# Programming_Interface.net
KiCad netlist of a schematic drawn in Altium Designer
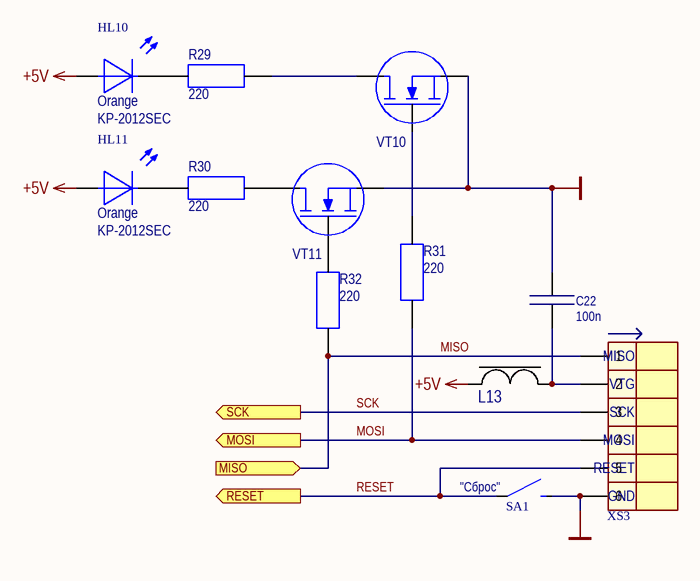
[diagram p0: Programming_Interface.SchDoc]

(export (version "E")
  (design (tool "Eeschema 10.0.6"))
  (components
    (comp (ref "C22")
      (value "100n")
      (footprint "SMDRC0805")
      (description "Generic capasitor non-polar")
      (fields (field (name "PARTNUMBER") "Capacitor 0805 100n"))
      (libsource (lib "library") (part "Capacitor"))
    )
    (comp (ref "HL10")
      (value "Orange")
      (footprint "Indicator:DIOMELF2012M")
      (description "Diod LED SMD Orange")
      (fields (field (name "MANUFACTURERPARTNUMBER") "KP-2012SEC"))
      (libsource (lib "Indicator") (part "LED1_O"))
    )
    (comp (ref "HL11")
      (value "Orange")
      (footprint "Indicator:DIOMELF2012M")
      (description "Diod LED SMD Orange")
      (fields (field (name "MANUFACTURERPARTNUMBER") "KP-2012SEC"))
      (libsource (lib "Indicator") (part "LED1_O"))
    )
    (comp (ref "L13")
      (value "MPZ1608S181A")
      (footprint "Inductor:INDC0603X03M")
      (description "Ferrite Bead")
      (libsource (lib "Inductor") (part "Ferrite Bead"))
    )
    (comp (ref "R29")
      (value "220")
      (footprint "SMDRC0805")
      (description "Generic resistor")
      (fields (field (name "PARTNUMBER") "Resistor 0805 220"))
      (libsource (lib "") (part "Resistor_1"))
    )
    (comp (ref "R30")
      (value "220")
      (footprint "SMDRC0805")
      (description "Generic resistor")
      (fields (field (name "PARTNUMBER") "Resistor 0805 220"))
      (libsource (lib "") (part "Resistor_1"))
    )
    (comp (ref "R31")
      (value "220")
      (footprint "SMDRC0805")
      (description "Generic resistor")
      (fields (field (name "PARTNUMBER") "Resistor 0805 220"))
      (libsource (lib "library") (part "Resistor"))
    )
    (comp (ref "R32")
      (value "220")
      (footprint "SMDRC0805")
      (description "Generic resistor")
      (fields (field (name "PARTNUMBER") "Resistor 0805 220"))
      (libsource (lib "library") (part "Resistor"))
    )
    (comp (ref "SA1")
      (value "DTSM20-4.3")
      (footprint "Switch:DTSM20")
      (description "Switch open")
      (fields (field (name "MANUFACTURER") "Diptronics"))
      (libsource (lib "Switch") (part "Switch1_DTSM20-4.3"))
    )
    (comp (ref "VT10")
      (value "2N7002")
      (footprint "Standard:SOT23 (TO-236AB)")
      (description "60V, 300mA N-channel Trench MOSFET")
      (libsource (lib "Transistor") (part "2N7002 n-MOSFET"))
    )
    (comp (ref "VT11")
      (value "2N7002")
      (footprint "Standard:SOT23 (TO-236AB)")
      (description "60V, 300mA N-channel Trench MOSFET")
      (libsource (lib "Transistor") (part "2N7002 n-MOSFET"))
    )
    (comp (ref "XS3")
      (value "IDC-06M")
      (footprint "Connector:IDC-06M")
      (description "SPI connector")
      (libsource (lib "Connector") (part "Con6_M IDC-06M_SPI"))
    )
  )
  (nets
    (net (code "1") (name "+5V") (class "Default")
      (node (ref "HL10") (pin "1") (pinfunction "1_1") (pintype "passive"))
      (node (ref "HL11") (pin "1") (pinfunction "1_1") (pintype "passive"))
      (node (ref "L13") (pin "1") (pinfunction "1_1") (pintype "passive"))
    )
    (net (code "2") (name "/MISO") (class "Default")
      (node (ref "R32") (pin "1") (pinfunction "1_1") (pintype "passive"))
      (node (ref "XS3") (pin "1") (pinfunction "1_1") (pintype "passive"))
    )
    (net (code "3") (name "/MOSI") (class "Default")
      (node (ref "R31") (pin "1") (pinfunction "1_1") (pintype "passive"))
      (node (ref "XS3") (pin "4") (pinfunction "4_4") (pintype "passive"))
    )
    (net (code "4") (name "/RESET") (class "Default")
      (node (ref "SA1") (pin "1") (pinfunction "1_1") (pintype "passive"))
      (node (ref "XS3") (pin "5") (pinfunction "5_5") (pintype "passive"))
    )
    (net (code "5") (name "/SCK") (class "Default")
      (node (ref "XS3") (pin "3") (pinfunction "3_3") (pintype "passive"))
    )
    (net (code "6") (name "GND") (class "Default")
      (node (ref "C22") (pin "2") (pintype "passive"))
      (node (ref "SA1") (pin "2") (pinfunction "2_2") (pintype "passive"))
      (node (ref "VT10") (pin "2") (pinfunction "S_2") (pintype "passive"))
      (node (ref "VT11") (pin "2") (pinfunction "S_2") (pintype "passive"))
      (node (ref "XS3") (pin "6") (pinfunction "6_6") (pintype "passive"))
    )
    (net (code "7") (name "Net-(C22-Pad1)") (class "Default")
      (node (ref "C22") (pin "1") (pintype "passive"))
      (node (ref "L13") (pin "2") (pinfunction "2_2") (pintype "passive"))
      (node (ref "XS3") (pin "2") (pinfunction "2_2") (pintype "passive"))
    )
    (net (code "8") (name "Net-(HL10-Pad2)") (class "Default")
      (node (ref "HL10") (pin "2") (pinfunction "2_2") (pintype "passive"))
      (node (ref "R29") (pin "2") (pinfunction "2_2") (pintype "passive"))
    )
    (net (code "9") (name "Net-(HL11-Pad2)") (class "Default")
      (node (ref "HL11") (pin "2") (pinfunction "2_2") (pintype "passive"))
      (node (ref "R30") (pin "2") (pinfunction "2_2") (pintype "passive"))
    )
    (net (code "10") (name "Net-(VT10-D)") (class "Default")
      (node (ref "R29") (pin "1") (pinfunction "1_1") (pintype "passive"))
      (node (ref "VT10") (pin "3") (pinfunction "D_3") (pintype "passive"))
    )
    (net (code "11") (name "Net-(VT10-G)") (class "Default")
      (node (ref "R31") (pin "2") (pinfunction "2_2") (pintype "passive"))
      (node (ref "VT10") (pin "1") (pinfunction "G_1") (pintype "passive"))
    )
    (net (code "12") (name "Net-(VT11-D)") (class "Default")
      (node (ref "R30") (pin "1") (pinfunction "1_1") (pintype "passive"))
      (node (ref "VT11") (pin "3") (pinfunction "D_3") (pintype "passive"))
    )
    (net (code "13") (name "Net-(VT11-G)") (class "Default")
      (node (ref "R32") (pin "2") (pinfunction "2_2") (pintype "passive"))
      (node (ref "VT11") (pin "1") (pinfunction "G_1") (pintype "passive"))
    )
  )
)
